# switch_control.net
KiCad netlist of a schematic drawn in Altium Designer
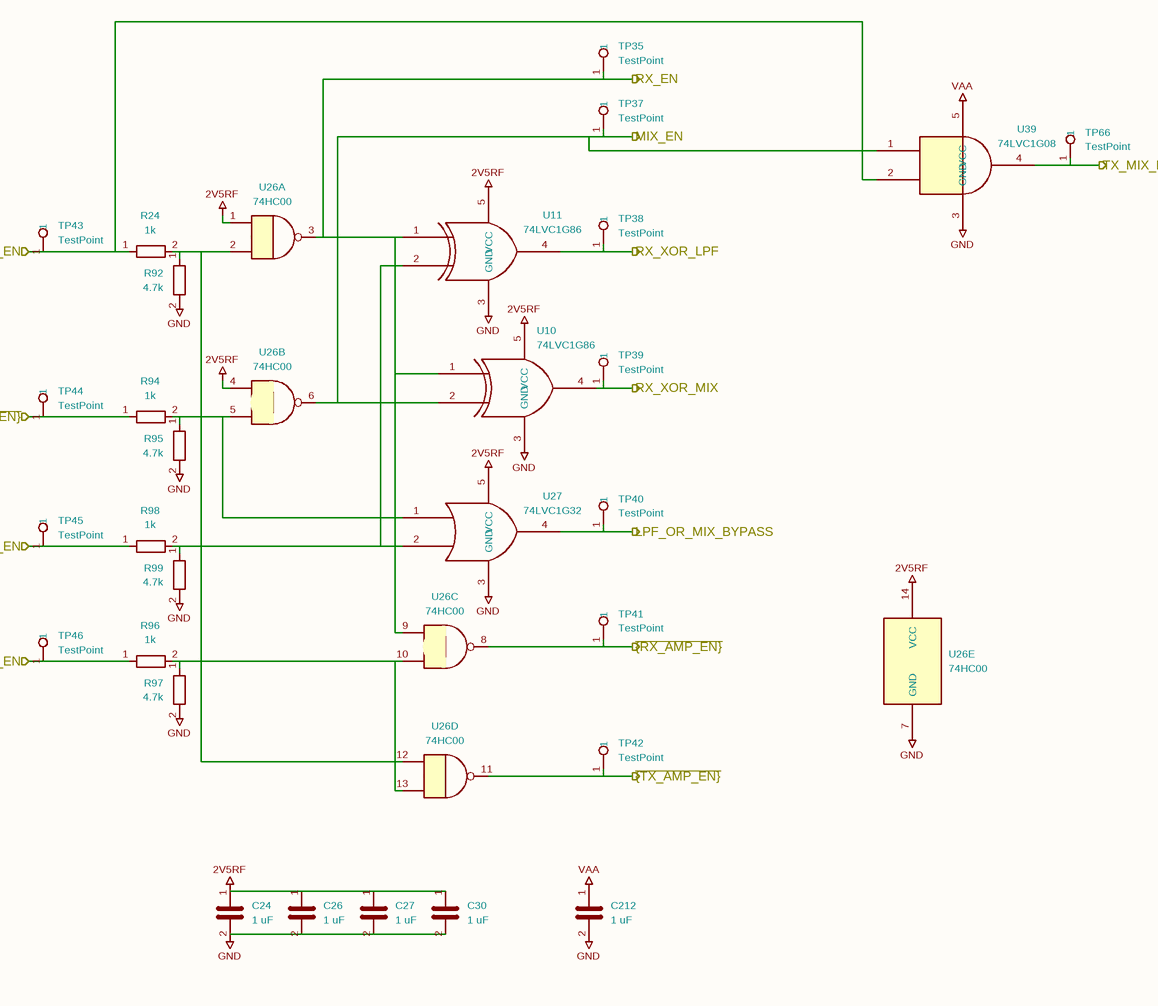
[diagram p0: switch_control.SchDoc]

(export (version "E")
  (design (tool "Eeschema 10.0.6"))
  (components
    (comp (ref "C24")
      (value "1 uF")
      (footprint "C_0201_0603Metric")
      (description "CAP CER 1UF 10V X5R 0201")
      (fields (field (name "MANUFACTURER") "Murata") (field (name "PART NUMBER") "GRM033R61A105ME44D"))
      (libsource (lib "Device") (part "C"))
    )
    (comp (ref "C26")
      (value "1 uF")
      (footprint "C_0201_0603Metric")
      (description "CAP CER 1UF 10V X5R 0201")
      (fields (field (name "MANUFACTURER") "Murata") (field (name "PART NUMBER") "GRM033R61A105ME44D"))
      (libsource (lib "Device") (part "C"))
    )
    (comp (ref "C27")
      (value "1 uF")
      (footprint "C_0201_0603Metric")
      (description "CAP CER 1UF 10V X5R 0201")
      (fields (field (name "MANUFACTURER") "Murata") (field (name "PART NUMBER") "GRM033R61A105ME44D"))
      (libsource (lib "Device") (part "C"))
    )
    (comp (ref "C30")
      (value "1 uF")
      (footprint "C_0201_0603Metric")
      (description "CAP CER 1UF 10V X5R 0201")
      (fields (field (name "MANUFACTURER") "Murata") (field (name "PART NUMBER") "GRM033R61A105ME44D"))
      (libsource (lib "Device") (part "C"))
    )
    (comp (ref "C212")
      (value "1 uF")
      (footprint "C_0201_0603Metric")
      (description "CAP CER 1UF 10V X5R 0201")
      (fields (field (name "MANUFACTURER") "Murata") (field (name "PART NUMBER") "GRM033R61A105ME44D"))
      (libsource (lib "Device") (part "C"))
    )
    (comp (ref "R24")
      (value "1k")
      (footprint "R_0201_0603Metric")
      (description "RES 1K OHM 1% 1/20W 0201")
      (fields (field (name "MANUFACTURER") "Yageo") (field (name "PART NUMBER") "RC0201FR-071KL"))
      (libsource (lib "") (part "R_1"))
    )
    (comp (ref "R92")
      (value "4.7k")
      (footprint "R_0201_0603Metric")
      (description "RES 4.7K OHM 1% 1/20W 0201")
      (fields (field (name "MANUFACTURER") "Yageo") (field (name "PART NUMBER") "RC0201FR-074K7L"))
      (libsource (lib "Device") (part "R"))
    )
    (comp (ref "R94")
      (value "1k")
      (footprint "R_0201_0603Metric")
      (description "RES 1K OHM 1% 1/20W 0201")
      (fields (field (name "MANUFACTURER") "Yageo") (field (name "PART NUMBER") "RC0201FR-071KL"))
      (libsource (lib "") (part "R_1"))
    )
    (comp (ref "R95")
      (value "4.7k")
      (footprint "R_0201_0603Metric")
      (description "RES 4.7K OHM 1% 1/20W 0201")
      (fields (field (name "MANUFACTURER") "Yageo") (field (name "PART NUMBER") "RC0201FR-074K7L"))
      (libsource (lib "Device") (part "R"))
    )
    (comp (ref "R96")
      (value "1k")
      (footprint "R_0201_0603Metric")
      (description "RES 1K OHM 1% 1/20W 0201")
      (fields (field (name "MANUFACTURER") "Yageo") (field (name "PART NUMBER") "RC0201FR-071KL"))
      (libsource (lib "") (part "R_1"))
    )
    (comp (ref "R97")
      (value "4.7k")
      (footprint "R_0201_0603Metric")
      (description "RES 4.7K OHM 1% 1/20W 0201")
      (fields (field (name "MANUFACTURER") "Yageo") (field (name "PART NUMBER") "RC0201FR-074K7L"))
      (libsource (lib "Device") (part "R"))
    )
    (comp (ref "R98")
      (value "1k")
      (footprint "R_0201_0603Metric")
      (description "RES 1K OHM 1% 1/20W 0201")
      (fields (field (name "MANUFACTURER") "Yageo") (field (name "PART NUMBER") "RC0201FR-071KL"))
      (libsource (lib "") (part "R_1"))
    )
    (comp (ref "R99")
      (value "4.7k")
      (footprint "R_0201_0603Metric")
      (description "RES 4.7K OHM 1% 1/20W 0201")
      (fields (field (name "MANUFACTURER") "Yageo") (field (name "PART NUMBER") "RC0201FR-074K7L"))
      (libsource (lib "Device") (part "R"))
    )
    (comp (ref "TP35")
      (value "TestPoint")
      (footprint "TestPoint_Pad_D1.0mm")
      (libsource (lib "Connector") (part "TestPoint"))
    )
    (comp (ref "TP37")
      (value "TestPoint")
      (footprint "TestPoint_Pad_D1.0mm")
      (libsource (lib "Connector") (part "TestPoint"))
    )
    (comp (ref "TP38")
      (value "TestPoint")
      (footprint "TestPoint_Pad_D1.0mm")
      (libsource (lib "Connector") (part "TestPoint"))
    )
    (comp (ref "TP39")
      (value "TestPoint")
      (footprint "TestPoint_Pad_D1.0mm")
      (libsource (lib "Connector") (part "TestPoint"))
    )
    (comp (ref "TP40")
      (value "TestPoint")
      (footprint "TestPoint_Pad_D1.0mm")
      (libsource (lib "Connector") (part "TestPoint"))
    )
    (comp (ref "TP41")
      (value "TestPoint")
      (footprint "TestPoint_Pad_D1.0mm")
      (libsource (lib "Connector") (part "TestPoint"))
    )
    (comp (ref "TP42")
      (value "TestPoint")
      (footprint "TestPoint_Pad_D1.0mm")
      (libsource (lib "Connector") (part "TestPoint"))
    )
    (comp (ref "TP43")
      (value "TestPoint")
      (footprint "TestPoint_Pad_D1.0mm")
      (libsource (lib "Connector") (part "TestPoint"))
    )
    (comp (ref "TP44")
      (value "TestPoint")
      (footprint "TestPoint_Pad_D1.0mm")
      (libsource (lib "Connector") (part "TestPoint"))
    )
    (comp (ref "TP45")
      (value "TestPoint")
      (footprint "TestPoint_Pad_D1.0mm")
      (libsource (lib "Connector") (part "TestPoint"))
    )
    (comp (ref "TP46")
      (value "TestPoint")
      (footprint "TestPoint_Pad_D1.0mm")
      (libsource (lib "Connector") (part "TestPoint"))
    )
    (comp (ref "TP66")
      (value "TestPoint")
      (footprint "TestPoint_Pad_D1.0mm")
      (libsource (lib "Connector") (part "TestPoint"))
    )
    (comp (ref "U10")
      (value "74LVC1G86")
      (footprint "SOT-353_SC-70-5")
      (description "IC GATE XOR 1CH 2-INP SC70-5")
      (fields (field (name "MANUFACTURER") "UMW") (field (name "PART NUMBER") "SN74LVC1G86DCKR"))
      (libsource (lib "74xGxx") (part "74LVC1G86"))
    )
    (comp (ref "U11")
      (value "74LVC1G86")
      (footprint "SOT-353_SC-70-5")
      (description "IC GATE XOR 1CH 2-INP SC70-5")
      (fields (field (name "MANUFACTURER") "UMW") (field (name "PART NUMBER") "SN74LVC1G86DCKR"))
      (libsource (lib "74xGxx") (part "74LVC1G86"))
    )
    (comp (ref "U26")
      (value "74HC00")
      (footprint "DHVQFN-14-1EP_2.5x3mm_P0.5mm_EP1x1.5mm")
      (description "IC GATE NAND 4CH 2-INP 14DHVQFN")
      (fields (field (name "MANUFACTURER") "Nexperia") (field (name "PART NUMBER") "74HC00BQ,115"))
      (libsource (lib "74xx") (part "74HC00"))
    )
    (comp (ref "U27")
      (value "74LVC1G32")
      (footprint "SOT-353_SC-70-5")
      (description "IC GATE OR 1CH 2-INP SC70-5")
      (fields (field (name "MANUFACTURER") "UMW") (field (name "PART NUMBER") "SN74LVC1G32DCKR"))
      (libsource (lib "74xGxx") (part "74LVC1G32"))
    )
    (comp (ref "U39")
      (value "74LVC1G08")
      (footprint "SOT-353_SC-70-5")
      (description "IC GATE AND 1CH 2-INP SC70-5")
      (fields (field (name "MANUFACTURER") "UMW") (field (name "PART NUMBER") "SN74LVC1G08DCKR"))
      (libsource (lib "74xGxx") (part "74LVC1G08"))
    )
  )
  (nets
    (net (code "1") (name "/LPF_EN") (class "Default")
      (node (ref "R98") (pin "1") (pinfunction "1_1") (pintype "passive"))
      (node (ref "TP45") (pin "1") (pinfunction "1_1") (pintype "passive"))
    )
    (net (code "2") (name "/LPF_OR_MIX_BYPASS") (class "Default")
      (node (ref "TP40") (pin "1") (pinfunction "1_1") (pintype "passive"))
      (node (ref "U27") (pin "4") (pinfunction "4_4") (pintype "passive"))
    )
    (net (code "3") (name "/MIX_EN") (class "Default")
      (node (ref "TP37") (pin "1") (pinfunction "1_1") (pintype "passive"))
      (node (ref "U10") (pin "2") (pinfunction "2_2") (pintype "passive"))
      (node (ref "U26") (pin "6") (pinfunction "6_6") (pintype "passive"))
      (node (ref "U39") (pin "1") (pinfunction "1_1") (pintype "passive"))
    )
    (net (code "4") (name "/RF_AMP_EN") (class "Default")
      (node (ref "R96") (pin "1") (pinfunction "1_1") (pintype "passive"))
      (node (ref "TP46") (pin "1") (pinfunction "1_1") (pintype "passive"))
    )
    (net (code "5") (name "/RX_EN") (class "Default")
      (node (ref "TP35") (pin "1") (pinfunction "1_1") (pintype "passive"))
      (node (ref "U10") (pin "1") (pinfunction "1_1") (pintype "passive"))
      (node (ref "U11") (pin "1") (pinfunction "1_1") (pintype "passive"))
      (node (ref "U26") (pin "3") (pinfunction "3_3") (pintype "passive"))
      (node (ref "U26") (pin "9") (pinfunction "9_9") (pintype "passive"))
    )
    (net (code "6") (name "/RX_XOR_LPF") (class "Default")
      (node (ref "TP38") (pin "1") (pinfunction "1_1") (pintype "passive"))
      (node (ref "U11") (pin "4") (pinfunction "4_4") (pintype "passive"))
    )
    (net (code "7") (name "/RX_XOR_MIX") (class "Default")
      (node (ref "TP39") (pin "1") (pinfunction "1_1") (pintype "passive"))
      (node (ref "U10") (pin "4") (pinfunction "4_4") (pintype "passive"))
    )
    (net (code "8") (name "/TX_EN") (class "Default")
      (node (ref "R24") (pin "1") (pinfunction "1_1") (pintype "passive"))
      (node (ref "TP43") (pin "1") (pinfunction "1_1") (pintype "passive"))
      (node (ref "U39") (pin "2") (pinfunction "2_2") (pintype "passive"))
    )
    (net (code "9") (name "/TX_MIX_EN") (class "Default")
      (node (ref "TP66") (pin "1") (pinfunction "1_1") (pintype "passive"))
      (node (ref "U39") (pin "4") (pinfunction "4_4") (pintype "passive"))
    )
    (net (code "10") (name "/~{{MIX_EN}}") (class "Default")
      (node (ref "R94") (pin "1") (pinfunction "1_1") (pintype "passive"))
      (node (ref "TP44") (pin "1") (pinfunction "1_1") (pintype "passive"))
    )
    (net (code "11") (name "/~{{RX_AMP_EN}}") (class "Default")
      (node (ref "TP41") (pin "1") (pinfunction "1_1") (pintype "passive"))
      (node (ref "U26") (pin "8") (pinfunction "8_8") (pintype "passive"))
    )
    (net (code "12") (name "/~{{TX_AMP_EN}}") (class "Default")
      (node (ref "TP42") (pin "1") (pinfunction "1_1") (pintype "passive"))
      (node (ref "U26") (pin "11") (pinfunction "11_11") (pintype "passive"))
    )
    (net (code "13") (name "2V5RF") (class "Default")
      (node (ref "C24") (pin "1") (pinfunction "1_1") (pintype "passive"))
      (node (ref "C26") (pin "1") (pinfunction "1_1") (pintype "passive"))
      (node (ref "C27") (pin "1") (pinfunction "1_1") (pintype "passive"))
      (node (ref "C30") (pin "1") (pinfunction "1_1") (pintype "passive"))
      (node (ref "U10") (pin "5") (pinfunction "VCC_5") (pintype "passive"))
      (node (ref "U11") (pin "5") (pinfunction "VCC_5") (pintype "passive"))
      (node (ref "U26") (pin "1") (pinfunction "1_1") (pintype "passive"))
      (node (ref "U26") (pin "14") (pinfunction "VCC_14") (pintype "passive"))
      (node (ref "U26") (pin "4") (pinfunction "4_4") (pintype "passive"))
      (node (ref "U27") (pin "5") (pinfunction "VCC_5") (pintype "passive"))
    )
    (net (code "14") (name "GND") (class "Default")
      (node (ref "C212") (pin "2") (pinfunction "2_2") (pintype "passive"))
      (node (ref "C24") (pin "2") (pinfunction "2_2") (pintype "passive"))
      (node (ref "C26") (pin "2") (pinfunction "2_2") (pintype "passive"))
      (node (ref "C27") (pin "2") (pinfunction "2_2") (pintype "passive"))
      (node (ref "C30") (pin "2") (pinfunction "2_2") (pintype "passive"))
      (node (ref "R92") (pin "2") (pinfunction "2_2") (pintype "passive"))
      (node (ref "R95") (pin "2") (pinfunction "2_2") (pintype "passive"))
      (node (ref "R97") (pin "2") (pinfunction "2_2") (pintype "passive"))
      (node (ref "R99") (pin "2") (pinfunction "2_2") (pintype "passive"))
      (node (ref "U10") (pin "3") (pinfunction "GND_3") (pintype "passive"))
      (node (ref "U11") (pin "3") (pinfunction "GND_3") (pintype "passive"))
      (node (ref "U26") (pin "7") (pinfunction "GND_7") (pintype "passive"))
      (node (ref "U27") (pin "3") (pinfunction "GND_3") (pintype "passive"))
      (node (ref "U39") (pin "3") (pinfunction "GND_3") (pintype "passive"))
    )
    (net (code "15") (name "Net-(R24-Pad2)") (class "Default")
      (node (ref "R24") (pin "2") (pinfunction "2_2") (pintype "passive"))
      (node (ref "R92") (pin "1") (pinfunction "1_1") (pintype "passive"))
      (node (ref "U26") (pin "12") (pinfunction "12_12") (pintype "passive"))
      (node (ref "U26") (pin "2") (pinfunction "2_2") (pintype "passive"))
    )
    (net (code "16") (name "Net-(R94-Pad2)") (class "Default")
      (node (ref "R94") (pin "2") (pinfunction "2_2") (pintype "passive"))
      (node (ref "R95") (pin "1") (pinfunction "1_1") (pintype "passive"))
      (node (ref "U26") (pin "5") (pinfunction "5_5") (pintype "passive"))
      (node (ref "U27") (pin "1") (pinfunction "1_1") (pintype "passive"))
    )
    (net (code "17") (name "Net-(R96-Pad2)") (class "Default")
      (node (ref "R96") (pin "2") (pinfunction "2_2") (pintype "passive"))
      (node (ref "R97") (pin "1") (pinfunction "1_1") (pintype "passive"))
      (node (ref "U26") (pin "10") (pinfunction "10_10") (pintype "passive"))
      (node (ref "U26") (pin "13") (pinfunction "13_13") (pintype "passive"))
    )
    (net (code "18") (name "Net-(R98-Pad2)") (class "Default")
      (node (ref "R98") (pin "2") (pinfunction "2_2") (pintype "passive"))
      (node (ref "R99") (pin "1") (pinfunction "1_1") (pintype "passive"))
      (node (ref "U11") (pin "2") (pinfunction "2_2") (pintype "passive"))
      (node (ref "U27") (pin "2") (pinfunction "2_2") (pintype "passive"))
    )
    (net (code "19") (name "VAA") (class "Default")
      (node (ref "C212") (pin "1") (pinfunction "1_1") (pintype "passive"))
      (node (ref "U39") (pin "5") (pinfunction "VCC_5") (pintype "passive"))
    )
  )
)
